# SmartCup1.net
KiCad netlist of a schematic drawn in EAGLE
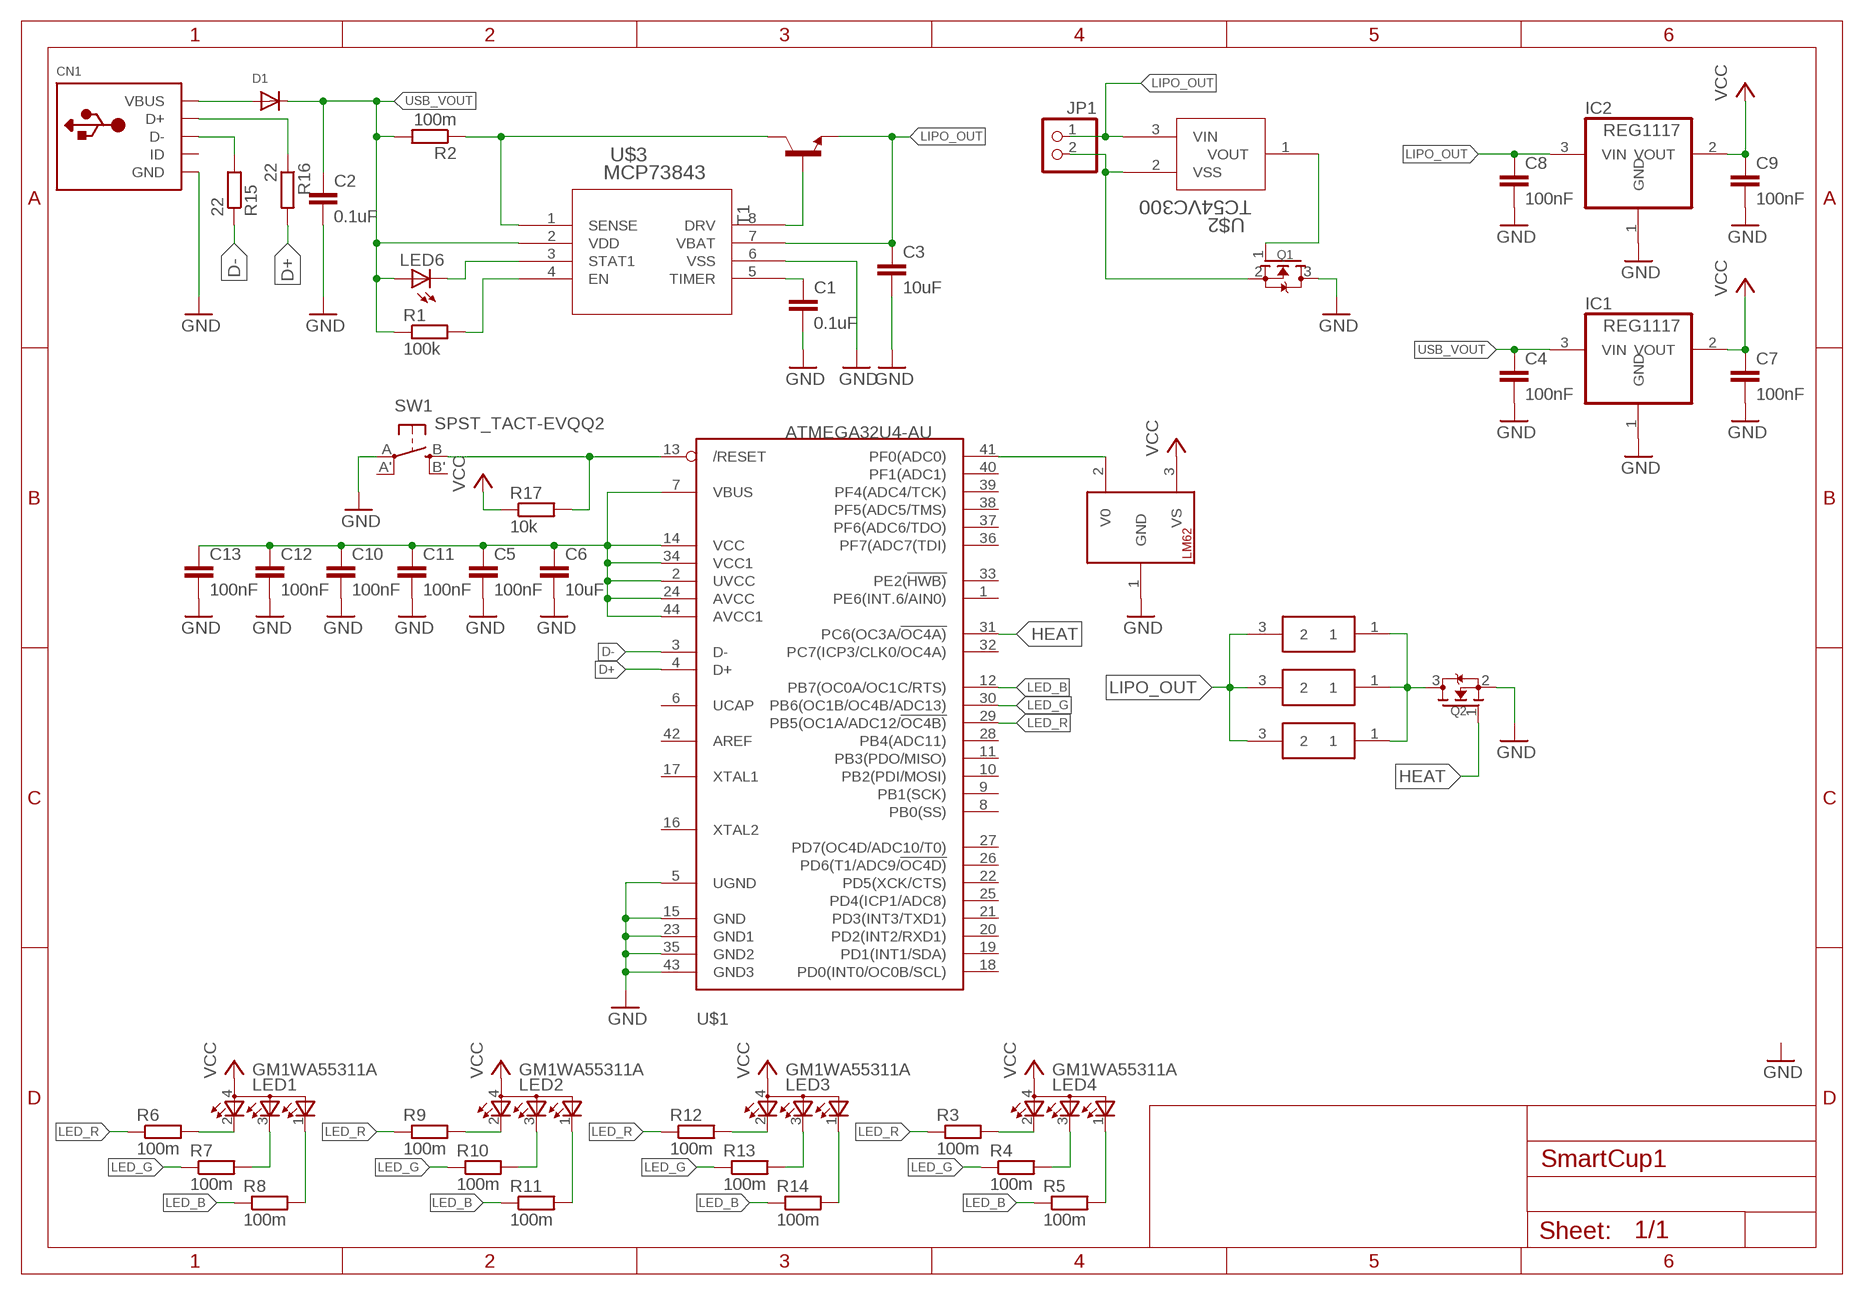
[diagram p0: schematic, sheet 1]

(export (version "E")
  (design (tool "Eeschema 10.0.6"))
  (components
    (comp (ref "C1")
      (value "0.1uF")
      (footprint "eagle-import:C0603")
      (libsource (lib "eagle-import") (part "C-EUC0603"))
    )
    (comp (ref "C2")
      (value "0.1uF")
      (footprint "eagle-import:C0603")
      (libsource (lib "eagle-import") (part "C-EUC0603"))
    )
    (comp (ref "C3")
      (value "10uF")
      (footprint "eagle-import:C0603")
      (libsource (lib "eagle-import") (part "C-EUC0603"))
    )
    (comp (ref "C4")
      (value "100nF")
      (footprint "eagle-import:C0603")
      (libsource (lib "eagle-import") (part "C-EUC0603"))
    )
    (comp (ref "C5")
      (value "100nF")
      (footprint "eagle-import:C0603")
      (libsource (lib "eagle-import") (part "C-EUC0603"))
    )
    (comp (ref "C6")
      (value "10uF")
      (footprint "eagle-import:C0805")
      (libsource (lib "eagle-import") (part "C-EUC0805"))
    )
    (comp (ref "C7")
      (value "100nF")
      (footprint "eagle-import:C0603")
      (libsource (lib "eagle-import") (part "C-EUC0603"))
    )
    (comp (ref "C8")
      (value "100nF")
      (footprint "eagle-import:C0603")
      (libsource (lib "eagle-import") (part "C-EUC0603"))
    )
    (comp (ref "C9")
      (value "100nF")
      (footprint "eagle-import:C0603")
      (libsource (lib "eagle-import") (part "C-EUC0603"))
    )
    (comp (ref "C10")
      (value "100nF")
      (footprint "eagle-import:C0603")
      (libsource (lib "eagle-import") (part "C-EUC0603"))
    )
    (comp (ref "C11")
      (value "100nF")
      (footprint "eagle-import:C0603")
      (libsource (lib "eagle-import") (part "C-EUC0603"))
    )
    (comp (ref "C12")
      (value "100nF")
      (footprint "eagle-import:C0603")
      (libsource (lib "eagle-import") (part "C-EUC0603"))
    )
    (comp (ref "C13")
      (value "100nF")
      (footprint "eagle-import:C0603")
      (libsource (lib "eagle-import") (part "C-EUC0603"))
    )
    (comp (ref "CN1")
      (value "USBMINIB")
      (footprint "eagle-import:USB-MINIB")
      (libsource (lib "eagle-import") (part "USBMINIB"))
    )
    (comp (ref "D1")
      (value "DIODE_SOD-123FL")
      (footprint "eagle-import:SOD-123FL")
      (libsource (lib "eagle-import") (part "DIODE_SOD-123FL"))
    )
    (comp (ref "IC1")
      (value "REG1117")
      (footprint "eagle-import:SOT223")
      (libsource (lib "eagle-import") (part "REG1117"))
    )
    (comp (ref "IC2")
      (value "REG1117")
      (footprint "eagle-import:SOT223")
      (libsource (lib "eagle-import") (part "REG1117"))
    )
    (comp (ref "JP1")
      (value "PINHD-1X2")
      (footprint "eagle-import:1X02")
      (libsource (lib "eagle-import") (part "PINHD-1X2"))
    )
    (comp (ref "LED1")
      (value "GM1WA55311A")
      (footprint "eagle-import:GM1WA55311A")
      (libsource (lib "eagle-import") (part "GM1WA55311A"))
    )
    (comp (ref "LED2")
      (value "GM1WA55311A")
      (footprint "eagle-import:GM1WA55311A")
      (libsource (lib "eagle-import") (part "GM1WA55311A"))
    )
    (comp (ref "LED3")
      (value "GM1WA55311A")
      (footprint "eagle-import:GM1WA55311A")
      (libsource (lib "eagle-import") (part "GM1WA55311A"))
    )
    (comp (ref "LED4")
      (value "GM1WA55311A")
      (footprint "eagle-import:GM1WA55311A")
      (libsource (lib "eagle-import") (part "GM1WA55311A"))
    )
    (comp (ref "LED6")
      (value "LEDCHIP-LED0603")
      (footprint "eagle-import:CHIP-LED0603")
      (libsource (lib "eagle-import") (part "LEDCHIP-LED0603"))
    )
    (comp (ref "Q1")
      (value "MOSFET-NREFLOW")
      (footprint "eagle-import:SOT23")
      (libsource (lib "eagle-import") (part "MOSFET-NREFLOW"))
    )
    (comp (ref "Q2")
      (value "MOSFET-NREFLOW")
      (footprint "eagle-import:SOT23")
      (libsource (lib "eagle-import") (part "MOSFET-NREFLOW"))
    )
    (comp (ref "R1")
      (value "100k")
      (footprint "eagle-import:R0603")
      (libsource (lib "eagle-import") (part "R-EU_R0603"))
    )
    (comp (ref "R2")
      (value "100m")
      (footprint "eagle-import:R0603")
      (libsource (lib "eagle-import") (part "R-EU_R0603"))
    )
    (comp (ref "R3")
      (value "100m")
      (footprint "eagle-import:R0603")
      (libsource (lib "eagle-import") (part "R-EU_R0603"))
    )
    (comp (ref "R4")
      (value "100m")
      (footprint "eagle-import:R0603")
      (libsource (lib "eagle-import") (part "R-EU_R0603"))
    )
    (comp (ref "R5")
      (value "100m")
      (footprint "eagle-import:R0603")
      (libsource (lib "eagle-import") (part "R-EU_R0603"))
    )
    (comp (ref "R6")
      (value "100m")
      (footprint "eagle-import:R0603")
      (libsource (lib "eagle-import") (part "R-EU_R0603"))
    )
    (comp (ref "R7")
      (value "100m")
      (footprint "eagle-import:R0603")
      (libsource (lib "eagle-import") (part "R-EU_R0603"))
    )
    (comp (ref "R8")
      (value "100m")
      (footprint "eagle-import:R0603")
      (libsource (lib "eagle-import") (part "R-EU_R0603"))
    )
    (comp (ref "R9")
      (value "100m")
      (footprint "eagle-import:R0603")
      (libsource (lib "eagle-import") (part "R-EU_R0603"))
    )
    (comp (ref "R10")
      (value "100m")
      (footprint "eagle-import:R0603")
      (libsource (lib "eagle-import") (part "R-EU_R0603"))
    )
    (comp (ref "R11")
      (value "100m")
      (footprint "eagle-import:R0603")
      (libsource (lib "eagle-import") (part "R-EU_R0603"))
    )
    (comp (ref "R12")
      (value "100m")
      (footprint "eagle-import:R0603")
      (libsource (lib "eagle-import") (part "R-EU_R0603"))
    )
    (comp (ref "R13")
      (value "100m")
      (footprint "eagle-import:R0603")
      (libsource (lib "eagle-import") (part "R-EU_R0603"))
    )
    (comp (ref "R14")
      (value "100m")
      (footprint "eagle-import:R0603")
      (libsource (lib "eagle-import") (part "R-EU_R0603"))
    )
    (comp (ref "R15")
      (value "22")
      (footprint "eagle-import:R0603")
      (libsource (lib "eagle-import") (part "R-EU_R0603"))
    )
    (comp (ref "R16")
      (value "22")
      (footprint "eagle-import:R0603")
      (libsource (lib "eagle-import") (part "R-EU_R0603"))
    )
    (comp (ref "R17")
      (value "10k")
      (footprint "eagle-import:R0603")
      (libsource (lib "eagle-import") (part "R-EU_R0603"))
    )
    (comp (ref "SW1")
      (value "SPST_TACT-EVQQ2")
      (footprint "eagle-import:EVQ-Q2")
      (libsource (lib "eagle-import") (part "SPST_TACT-EVQQ2"))
    )
    (comp (ref "T1")
      (value "-NPN-SOT23-EBC")
      (footprint "eagle-import:SOT23-EBC")
      (libsource (lib "eagle-import") (part "-NPN-SOT23-EBC"))
    )
    (comp (ref "U$1")
      (value "ATMEGA32U4-AU")
      (footprint "eagle-import:TQFP44")
      (libsource (lib "eagle-import") (part "ATMEGA32U4-AU"))
    )
    (comp (ref "U$2")
      (value "TC54VC300")
      (footprint "eagle-import:SOT23")
      (libsource (lib "eagle-import") (part "TC54VC300"))
    )
    (comp (ref "U$3")
      (value "MCP73843")
      (footprint "eagle-import:MSOP8_MC")
      (libsource (lib "eagle-import") (part "MCP73843"))
    )
    (comp (ref "U$4")
      (value "LM62TO-92")
      (footprint "eagle-import:TO92-")
      (libsource (lib "eagle-import") (part "LM62TO-92"))
    )
    (comp (ref "U$6")
      (value "BOURNS_PWR")
      (footprint "eagle-import:DPAK")
      (libsource (lib "eagle-import") (part "BOURNS_PWR"))
    )
    (comp (ref "U$7")
      (value "BOURNS_PWR")
      (footprint "eagle-import:DPAK")
      (libsource (lib "eagle-import") (part "BOURNS_PWR"))
    )
    (comp (ref "U$8")
      (value "BOURNS_PWR")
      (footprint "eagle-import:DPAK")
      (libsource (lib "eagle-import") (part "BOURNS_PWR"))
    )
  )
  (nets
    (net (code "1") (name "D+") (class "Default")
      (node (ref "R16") (pin "2") (pinfunction "2_2") (pintype "passive"))
      (node (ref "U$1") (pin "4") (pinfunction "D+_4") (pintype "bidirectional"))
    )
    (net (code "2") (name "D-") (class "Default")
      (node (ref "R15") (pin "1") (pinfunction "1_1") (pintype "passive"))
      (node (ref "U$1") (pin "3") (pinfunction "D-_3") (pintype "bidirectional"))
    )
    (net (code "3") (name "GND") (class "Default")
      (node (ref "C1") (pin "2") (pinfunction "2_2") (pintype "passive"))
      (node (ref "C10") (pin "2") (pinfunction "2_2") (pintype "passive"))
      (node (ref "C11") (pin "2") (pinfunction "2_2") (pintype "passive"))
      (node (ref "C12") (pin "2") (pinfunction "2_2") (pintype "passive"))
      (node (ref "C13") (pin "2") (pinfunction "2_2") (pintype "passive"))
      (node (ref "C2") (pin "2") (pinfunction "2_2") (pintype "passive"))
      (node (ref "C3") (pin "2") (pinfunction "2_2") (pintype "passive"))
      (node (ref "C4") (pin "2") (pinfunction "2_2") (pintype "passive"))
      (node (ref "C5") (pin "2") (pinfunction "2_2") (pintype "passive"))
      (node (ref "C6") (pin "2") (pinfunction "2_2") (pintype "passive"))
      (node (ref "C7") (pin "2") (pinfunction "2_2") (pintype "passive"))
      (node (ref "C8") (pin "2") (pinfunction "2_2") (pintype "passive"))
      (node (ref "C9") (pin "2") (pinfunction "2_2") (pintype "passive"))
      (node (ref "CN1") (pin "GND") (pinfunction "GND_GND") (pintype "power_in"))
      (node (ref "IC1") (pin "1") (pinfunction "GND_1") (pintype "power_in"))
      (node (ref "IC2") (pin "1") (pinfunction "GND_1") (pintype "power_in"))
      (node (ref "Q1") (pin "3") (pinfunction "D_3") (pintype "bidirectional"))
      (node (ref "Q2") (pin "2") (pinfunction "S_2") (pintype "bidirectional"))
      (node (ref "SW1") (pin "A") (pinfunction "P_A") (pintype "passive"))
      (node (ref "U$1") (pin "15") (pinfunction "GND_15") (pintype "bidirectional"))
      (node (ref "U$1") (pin "23") (pinfunction "GND1_23") (pintype "bidirectional"))
      (node (ref "U$1") (pin "35") (pinfunction "GND2_35") (pintype "bidirectional"))
      (node (ref "U$1") (pin "43") (pinfunction "GND3_43") (pintype "bidirectional"))
      (node (ref "U$1") (pin "5") (pinfunction "UGND_5") (pintype "bidirectional"))
      (node (ref "U$3") (pin "6") (pinfunction "VSS_6") (pintype "passive"))
      (node (ref "U$4") (pin "1") (pinfunction "GND_1") (pintype "bidirectional"))
    )
    (net (code "4") (name "HEAT") (class "Default")
      (node (ref "Q2") (pin "1") (pinfunction "G_1") (pintype "bidirectional"))
      (node (ref "U$1") (pin "31") (pinfunction "PC6(OC3A/~{OC4A})_31") (pintype "bidirectional"))
    )
    (net (code "5") (name "LED_B") (class "Default")
      (node (ref "R11") (pin "1") (pinfunction "1_1") (pintype "passive"))
      (node (ref "R14") (pin "1") (pinfunction "1_1") (pintype "passive"))
      (node (ref "R5") (pin "1") (pinfunction "1_1") (pintype "passive"))
      (node (ref "R8") (pin "1") (pinfunction "1_1") (pintype "passive"))
      (node (ref "U$1") (pin "12") (pinfunction "PB7(OC0A/OC1C/RTS)_12") (pintype "bidirectional"))
    )
    (net (code "6") (name "LED_G") (class "Default")
      (node (ref "R10") (pin "1") (pinfunction "1_1") (pintype "passive"))
      (node (ref "R13") (pin "1") (pinfunction "1_1") (pintype "passive"))
      (node (ref "R4") (pin "1") (pinfunction "1_1") (pintype "passive"))
      (node (ref "R7") (pin "1") (pinfunction "1_1") (pintype "passive"))
      (node (ref "U$1") (pin "30") (pinfunction "PB6(OC1B/OC4B/ADC13)_30") (pintype "bidirectional"))
    )
    (net (code "7") (name "LED_R") (class "Default")
      (node (ref "R12") (pin "1") (pinfunction "1_1") (pintype "passive"))
      (node (ref "R3") (pin "1") (pinfunction "1_1") (pintype "passive"))
      (node (ref "R6") (pin "1") (pinfunction "1_1") (pintype "passive"))
      (node (ref "R9") (pin "1") (pinfunction "1_1") (pintype "passive"))
      (node (ref "U$1") (pin "29") (pinfunction "PB5(OC1A/ADC12/~{OC4B})_29") (pintype "bidirectional"))
    )
    (net (code "8") (name "LIPO_OUT") (class "Default")
      (node (ref "C3") (pin "1") (pinfunction "1_1") (pintype "passive"))
      (node (ref "C8") (pin "1") (pinfunction "1_1") (pintype "passive"))
      (node (ref "IC2") (pin "3") (pinfunction "VIN_3") (pintype "input"))
      (node (ref "JP1") (pin "1") (pinfunction "1_1") (pintype "passive"))
      (node (ref "T1") (pin "E") (pinfunction "E_E") (pintype "passive"))
      (node (ref "U$2") (pin "3") (pinfunction "VIN_3") (pintype "passive"))
      (node (ref "U$3") (pin "7") (pinfunction "VBAT_7") (pintype "passive"))
      (node (ref "U$6") (pin "3") (pinfunction "2_3") (pintype "bidirectional"))
      (node (ref "U$7") (pin "3") (pinfunction "2_3") (pintype "bidirectional"))
      (node (ref "U$8") (pin "3") (pinfunction "2_3") (pintype "bidirectional"))
    )
    (net (code "9") (name "Net-(CN1-PadD+)") (class "Default")
      (node (ref "CN1") (pin "D+") (pinfunction "D+_D+") (pintype "bidirectional"))
      (node (ref "R16") (pin "1") (pinfunction "1_1") (pintype "passive"))
    )
    (net (code "10") (name "Net-(CN1-PadD-)") (class "Default")
      (node (ref "CN1") (pin "D-") (pinfunction "D-_D-") (pintype "bidirectional"))
      (node (ref "R15") (pin "2") (pinfunction "2_2") (pintype "passive"))
    )
    (net (code "11") (name "Net-(CN1-PadVBUS)") (class "Default")
      (node (ref "CN1") (pin "VBUS") (pinfunction "VBUS_VBUS") (pintype "power_in"))
      (node (ref "D1") (pin "A") (pinfunction "A_A") (pintype "passive"))
    )
    (net (code "12") (name "Net-(LED1-CBLUE)") (class "Default")
      (node (ref "LED1") (pin "3") (pinfunction "CBLUE_3") (pintype "passive"))
      (node (ref "R7") (pin "2") (pinfunction "2_2") (pintype "passive"))
    )
    (net (code "13") (name "Net-(LED1-CGREEN)") (class "Default")
      (node (ref "LED1") (pin "1") (pinfunction "CGREEN_1") (pintype "passive"))
      (node (ref "R8") (pin "2") (pinfunction "2_2") (pintype "passive"))
    )
    (net (code "14") (name "Net-(LED1-CRED)") (class "Default")
      (node (ref "LED1") (pin "2") (pinfunction "CRED_2") (pintype "passive"))
      (node (ref "R6") (pin "2") (pinfunction "2_2") (pintype "passive"))
    )
    (net (code "15") (name "Net-(LED2-CBLUE)") (class "Default")
      (node (ref "LED2") (pin "3") (pinfunction "CBLUE_3") (pintype "passive"))
      (node (ref "R10") (pin "2") (pinfunction "2_2") (pintype "passive"))
    )
    (net (code "16") (name "Net-(LED2-CGREEN)") (class "Default")
      (node (ref "LED2") (pin "1") (pinfunction "CGREEN_1") (pintype "passive"))
      (node (ref "R11") (pin "2") (pinfunction "2_2") (pintype "passive"))
    )
    (net (code "17") (name "Net-(LED2-CRED)") (class "Default")
      (node (ref "LED2") (pin "2") (pinfunction "CRED_2") (pintype "passive"))
      (node (ref "R9") (pin "2") (pinfunction "2_2") (pintype "passive"))
    )
    (net (code "18") (name "Net-(LED3-CBLUE)") (class "Default")
      (node (ref "LED3") (pin "3") (pinfunction "CBLUE_3") (pintype "passive"))
      (node (ref "R13") (pin "2") (pinfunction "2_2") (pintype "passive"))
    )
    (net (code "19") (name "Net-(LED3-CGREEN)") (class "Default")
      (node (ref "LED3") (pin "1") (pinfunction "CGREEN_1") (pintype "passive"))
      (node (ref "R14") (pin "2") (pinfunction "2_2") (pintype "passive"))
    )
    (net (code "20") (name "Net-(LED3-CRED)") (class "Default")
      (node (ref "LED3") (pin "2") (pinfunction "CRED_2") (pintype "passive"))
      (node (ref "R12") (pin "2") (pinfunction "2_2") (pintype "passive"))
    )
    (net (code "21") (name "Net-(LED4-CBLUE)") (class "Default")
      (node (ref "LED4") (pin "3") (pinfunction "CBLUE_3") (pintype "passive"))
      (node (ref "R4") (pin "2") (pinfunction "2_2") (pintype "passive"))
    )
    (net (code "22") (name "Net-(LED4-CGREEN)") (class "Default")
      (node (ref "LED4") (pin "1") (pinfunction "CGREEN_1") (pintype "passive"))
      (node (ref "R5") (pin "2") (pinfunction "2_2") (pintype "passive"))
    )
    (net (code "23") (name "Net-(LED4-CRED)") (class "Default")
      (node (ref "LED4") (pin "2") (pinfunction "CRED_2") (pintype "passive"))
      (node (ref "R3") (pin "2") (pinfunction "2_2") (pintype "passive"))
    )
    (net (code "24") (name "Net-(Q1-G)") (class "Default")
      (node (ref "Q1") (pin "1") (pinfunction "G_1") (pintype "bidirectional"))
      (node (ref "U$2") (pin "1") (pinfunction "VOUT_1") (pintype "passive"))
    )
    (net (code "25") (name "Net-(Q1-S)") (class "Default")
      (node (ref "JP1") (pin "2") (pinfunction "2_2") (pintype "passive"))
      (node (ref "Q1") (pin "2") (pinfunction "S_2") (pintype "bidirectional"))
      (node (ref "U$2") (pin "2") (pinfunction "VSS_2") (pintype "passive"))
    )
    (net (code "26") (name "Net-(Q2-D)") (class "Default")
      (node (ref "Q2") (pin "3") (pinfunction "D_3") (pintype "bidirectional"))
      (node (ref "U$6") (pin "1") (pinfunction "1_1") (pintype "bidirectional"))
      (node (ref "U$7") (pin "1") (pinfunction "1_1") (pintype "bidirectional"))
      (node (ref "U$8") (pin "1") (pinfunction "1_1") (pintype "bidirectional"))
    )
    (net (code "27") (name "Net-(SW1-S)") (class "Default")
      (node (ref "R17") (pin "2") (pinfunction "2_2") (pintype "passive"))
      (node (ref "SW1") (pin "B") (pinfunction "S_B") (pintype "passive"))
      (node (ref "U$1") (pin "13") (pinfunction "/RESET_13") (pintype "bidirectional"))
    )
    (net (code "28") (name "Net-(U$1-AVCC)") (class "Default")
      (node (ref "C10") (pin "1") (pinfunction "1_1") (pintype "passive"))
      (node (ref "C11") (pin "1") (pinfunction "1_1") (pintype "passive"))
      (node (ref "C12") (pin "1") (pinfunction "1_1") (pintype "passive"))
      (node (ref "C13") (pin "1") (pinfunction "1_1") (pintype "passive"))
      (node (ref "C5") (pin "1") (pinfunction "1_1") (pintype "passive"))
      (node (ref "C6") (pin "1") (pinfunction "1_1") (pintype "passive"))
      (node (ref "U$1") (pin "14") (pinfunction "VCC_14") (pintype "bidirectional"))
      (node (ref "U$1") (pin "2") (pinfunction "UVCC_2") (pintype "bidirectional"))
      (node (ref "U$1") (pin "24") (pinfunction "AVCC_24") (pintype "bidirectional"))
      (node (ref "U$1") (pin "34") (pinfunction "VCC1_34") (pintype "bidirectional"))
      (node (ref "U$1") (pin "44") (pinfunction "AVCC1_44") (pintype "bidirectional"))
      (node (ref "U$1") (pin "7") (pinfunction "VBUS_7") (pintype "bidirectional"))
    )
    (net (code "29") (name "Net-(U$1-PF0(ADC0))") (class "Default")
      (node (ref "U$1") (pin "41") (pinfunction "PF0(ADC0)_41") (pintype "bidirectional"))
      (node (ref "U$4") (pin "2") (pinfunction "V0_2") (pintype "bidirectional"))
    )
    (net (code "30") (name "Net-(U$3-DRV)") (class "Default")
      (node (ref "T1") (pin "B") (pinfunction "B_B") (pintype "passive"))
      (node (ref "U$3") (pin "8") (pinfunction "DRV_8") (pintype "passive"))
    )
    (net (code "31") (name "Net-(U$3-EN)") (class "Default")
      (node (ref "R1") (pin "2") (pinfunction "2_2") (pintype "passive"))
      (node (ref "U$3") (pin "4") (pinfunction "EN_4") (pintype "passive"))
    )
    (net (code "32") (name "Net-(U$3-SENSE)") (class "Default")
      (node (ref "R2") (pin "1") (pinfunction "1_1") (pintype "passive"))
      (node (ref "T1") (pin "C") (pinfunction "C_C") (pintype "passive"))
      (node (ref "U$3") (pin "1") (pinfunction "SENSE_1") (pintype "passive"))
    )
    (net (code "33") (name "Net-(U$3-STAT1)") (class "Default")
      (node (ref "LED6") (pin "C") (pinfunction "C_C") (pintype "passive"))
      (node (ref "U$3") (pin "3") (pinfunction "STAT1_3") (pintype "passive"))
    )
    (net (code "34") (name "Net-(U$3-TIMER)") (class "Default")
      (node (ref "C1") (pin "1") (pinfunction "1_1") (pintype "passive"))
      (node (ref "U$3") (pin "5") (pinfunction "TIMER_5") (pintype "passive"))
    )
    (net (code "35") (name "USB_VOUT") (class "Default")
      (node (ref "C2") (pin "1") (pinfunction "1_1") (pintype "passive"))
      (node (ref "C4") (pin "1") (pinfunction "1_1") (pintype "passive"))
      (node (ref "D1") (pin "C") (pinfunction "C_C") (pintype "passive"))
      (node (ref "IC1") (pin "3") (pinfunction "VIN_3") (pintype "input"))
      (node (ref "LED6") (pin "A") (pinfunction "A_A") (pintype "passive"))
      (node (ref "R1") (pin "1") (pinfunction "1_1") (pintype "passive"))
      (node (ref "R2") (pin "2") (pinfunction "2_2") (pintype "passive"))
      (node (ref "U$3") (pin "2") (pinfunction "VDD_2") (pintype "passive"))
    )
    (net (code "36") (name "VCC") (class "Default")
      (node (ref "C7") (pin "1") (pinfunction "1_1") (pintype "passive"))
      (node (ref "C9") (pin "1") (pinfunction "1_1") (pintype "passive"))
      (node (ref "IC1") (pin "2") (pinfunction "VOUT_2") (pintype "output"))
      (node (ref "IC2") (pin "2") (pinfunction "VOUT_2") (pintype "output"))
      (node (ref "LED1") (pin "4") (pinfunction "A_4") (pintype "passive"))
      (node (ref "LED2") (pin "4") (pinfunction "A_4") (pintype "passive"))
      (node (ref "LED3") (pin "4") (pinfunction "A_4") (pintype "passive"))
      (node (ref "LED4") (pin "4") (pinfunction "A_4") (pintype "passive"))
      (node (ref "R17") (pin "1") (pinfunction "1_1") (pintype "passive"))
      (node (ref "U$4") (pin "3") (pinfunction "VS_3") (pintype "bidirectional"))
    )
    (net (code "37") (name "unconnected-(CN1-PadID)") (class "Default")
      (node (ref "CN1") (pin "ID") (pinfunction "ID_ID") (pintype "bidirectional"))
    )
    (net (code "38") (name "unconnected-(SW1-P1-PadA')") (class "Default")
      (node (ref "SW1") (pin "A'") (pinfunction "P1_A'") (pintype "passive"))
    )
    (net (code "39") (name "unconnected-(SW1-S1-PadB')") (class "Default")
      (node (ref "SW1") (pin "B'") (pinfunction "S1_B'") (pintype "passive"))
    )
    (net (code "40") (name "unconnected-(U$1-AREF-Pad42)") (class "Default")
      (node (ref "U$1") (pin "42") (pinfunction "AREF_42") (pintype "bidirectional"))
    )
    (net (code "41") (name "unconnected-(U$1-PB0(SS)-Pad8)") (class "Default")
      (node (ref "U$1") (pin "8") (pinfunction "PB0(SS)_8") (pintype "bidirectional"))
    )
    (net (code "42") (name "unconnected-(U$1-PB1(SCK)-Pad9)") (class "Default")
      (node (ref "U$1") (pin "9") (pinfunction "PB1(SCK)_9") (pintype "bidirectional"))
    )
    (net (code "43") (name "unconnected-(U$1-PB2(PDI{slash}MOSI)-Pad10)") (class "Default")
      (node (ref "U$1") (pin "10") (pinfunction "PB2(PDI/MOSI)_10") (pintype "bidirectional"))
    )
    (net (code "44") (name "unconnected-(U$1-PB3(PDO{slash}MISO)-Pad11)") (class "Default")
      (node (ref "U$1") (pin "11") (pinfunction "PB3(PDO/MISO)_11") (pintype "bidirectional"))
    )
    (net (code "45") (name "unconnected-(U$1-PB4(ADC11)-Pad28)") (class "Default")
      (node (ref "U$1") (pin "28") (pinfunction "PB4(ADC11)_28") (pintype "bidirectional"))
    )
    (net (code "46") (name "unconnected-(U$1-PC7(ICP3{slash}CLK0{slash}OC4A)-Pad32)") (class "Default")
      (node (ref "U$1") (pin "32") (pinfunction "PC7(ICP3/CLK0/OC4A)_32") (pintype "bidirectional"))
    )
    (net (code "47") (name "unconnected-(U$1-PD0(INT0{slash}OC0B{slash}SCL)-Pad18)") (class "Default")
      (node (ref "U$1") (pin "18") (pinfunction "PD0(INT0/OC0B/SCL)_18") (pintype "bidirectional"))
    )
    (net (code "48") (name "unconnected-(U$1-PD1(INT1{slash}SDA)-Pad19)") (class "Default")
      (node (ref "U$1") (pin "19") (pinfunction "PD1(INT1/SDA)_19") (pintype "bidirectional"))
    )
    (net (code "49") (name "unconnected-(U$1-PD2(INT2{slash}RXD1)-Pad20)") (class "Default")
      (node (ref "U$1") (pin "20") (pinfunction "PD2(INT2/RXD1)_20") (pintype "bidirectional"))
    )
    (net (code "50") (name "unconnected-(U$1-PD3(INT3{slash}TXD1)-Pad21)") (class "Default")
      (node (ref "U$1") (pin "21") (pinfunction "PD3(INT3/TXD1)_21") (pintype "bidirectional"))
    )
    (net (code "51") (name "unconnected-(U$1-PD4(ICP1{slash}ADC8)-Pad25)") (class "Default")
      (node (ref "U$1") (pin "25") (pinfunction "PD4(ICP1/ADC8)_25") (pintype "bidirectional"))
    )
    (net (code "52") (name "unconnected-(U$1-PD5(XCK{slash}CTS)-Pad22)") (class "Default")
      (node (ref "U$1") (pin "22") (pinfunction "PD5(XCK/CTS)_22") (pintype "bidirectional"))
    )
    (net (code "53") (name "unconnected-(U$1-PD6(T1{slash}ADC9{slash}~{OC4D})-Pad26)") (class "Default")
      (node (ref "U$1") (pin "26") (pinfunction "PD6(T1/ADC9/~{OC4D})_26") (pintype "bidirectional"))
    )
    (net (code "54") (name "unconnected-(U$1-PD7(OC4D{slash}ADC10{slash}T0)-Pad27)") (class "Default")
      (node (ref "U$1") (pin "27") (pinfunction "PD7(OC4D/ADC10/T0)_27") (pintype "bidirectional"))
    )
    (net (code "55") (name "unconnected-(U$1-PE2(~{HWB})-Pad33)") (class "Default")
      (node (ref "U$1") (pin "33") (pinfunction "PE2(~{HWB})_33") (pintype "bidirectional"))
    )
    (net (code "56") (name "unconnected-(U$1-PE6(INT.6{slash}AIN0)-Pad1)") (class "Default")
      (node (ref "U$1") (pin "1") (pinfunction "PE6(INT.6/AIN0)_1") (pintype "bidirectional"))
    )
    (net (code "57") (name "unconnected-(U$1-PF1(ADC1)-Pad40)") (class "Default")
      (node (ref "U$1") (pin "40") (pinfunction "PF1(ADC1)_40") (pintype "bidirectional"))
    )
    (net (code "58") (name "unconnected-(U$1-PF4(ADC4{slash}TCK)-Pad39)") (class "Default")
      (node (ref "U$1") (pin "39") (pinfunction "PF4(ADC4/TCK)_39") (pintype "bidirectional"))
    )
    (net (code "59") (name "unconnected-(U$1-PF5(ADC5{slash}TMS)-Pad38)") (class "Default")
      (node (ref "U$1") (pin "38") (pinfunction "PF5(ADC5/TMS)_38") (pintype "bidirectional"))
    )
    (net (code "60") (name "unconnected-(U$1-PF6(ADC6{slash}TDO)-Pad37)") (class "Default")
      (node (ref "U$1") (pin "37") (pinfunction "PF6(ADC6/TDO)_37") (pintype "bidirectional"))
    )
    (net (code "61") (name "unconnected-(U$1-PF7(ADC7(TDI)-Pad36)") (class "Default")
      (node (ref "U$1") (pin "36") (pinfunction "PF7(ADC7(TDI)_36") (pintype "bidirectional"))
    )
    (net (code "62") (name "unconnected-(U$1-UCAP-Pad6)") (class "Default")
      (node (ref "U$1") (pin "6") (pinfunction "UCAP_6") (pintype "bidirectional"))
    )
    (net (code "63") (name "unconnected-(U$1-XTAL1-Pad17)") (class "Default")
      (node (ref "U$1") (pin "17") (pinfunction "XTAL1_17") (pintype "bidirectional"))
    )
    (net (code "64") (name "unconnected-(U$1-XTAL2-Pad16)") (class "Default")
      (node (ref "U$1") (pin "16") (pinfunction "XTAL2_16") (pintype "bidirectional"))
    )
  )
)
